# 5_-CONNECTORS.net
KiCad netlist of a schematic drawn in Altium Designer
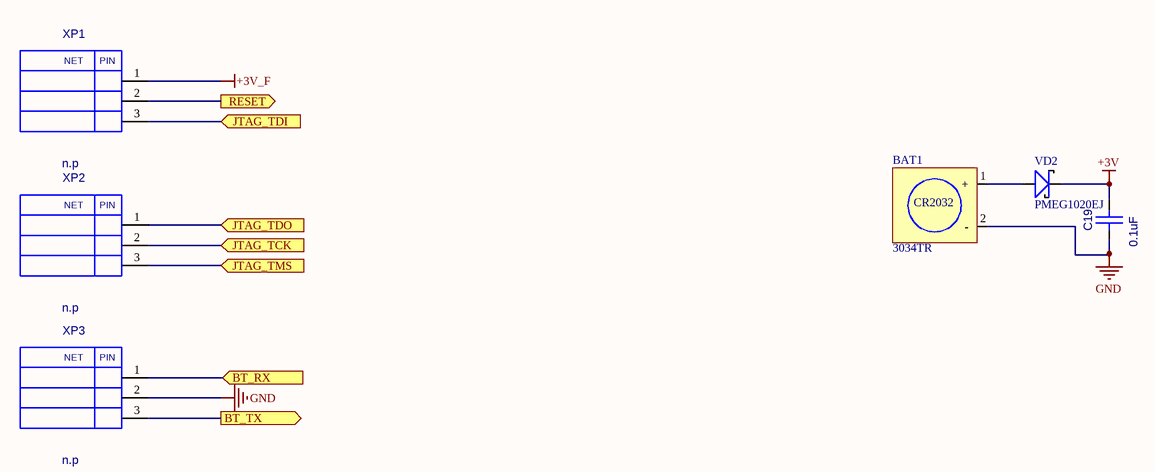
[diagram p0: [5]-CONNECTORS.SchDoc]

(export (version "E")
  (design (tool "Eeschema 10.0.6"))
  (components
    (comp (ref "BAT1")
      (value "3034TR")
      (footprint "3034-TR")
      (description "CR2032 holder smd")
      (libsource (lib "fizik_lib") (part "3034"))
    )
    (comp (ref "C19")
      (value "0.1uF")
      (footprint "CC0603")
      (description "CC0603")
      (libsource (lib "fizik_lib") (part "CC0603"))
    )
    (comp (ref "VD2")
      (value "PMEG1020EJ")
      (footprint "SOD323")
      (libsource (lib "fizik_lib") (part "PMEG2010"))
    )
    (comp (ref "XP1")
      (value "n.p")
      (footprint "PLS-03")
      (description "PLS03")
      (libsource (lib "fizik_lib") (part "PLS03"))
    )
    (comp (ref "XP2")
      (value "n.p")
      (footprint "PLS-03")
      (description "PLS03")
      (libsource (lib "fizik_lib") (part "PLS03"))
    )
    (comp (ref "XP3")
      (value "n.p")
      (footprint "PLS-03")
      (description "PLS03")
      (libsource (lib "fizik_lib") (part "PLS03"))
    )
  )
  (nets
    (net (code "1") (name "+3V") (class "Default")
      (node (ref "C19") (pin "2") (pinfunction "B_2") (pintype "passive"))
      (node (ref "VD2") (pin "2") (pinfunction "K_2") (pintype "passive"))
    )
    (net (code "2") (name "+3V_F") (class "Default")
      (node (ref "XP1") (pin "1") (pinfunction "1_1") (pintype "passive"))
    )
    (net (code "3") (name "/BT_RX") (class "Default")
      (node (ref "XP3") (pin "1") (pinfunction "1_1") (pintype "passive"))
    )
    (net (code "4") (name "/BT_TX") (class "Default")
      (node (ref "XP3") (pin "3") (pinfunction "3_3") (pintype "passive"))
    )
    (net (code "5") (name "/JTAG_TCK") (class "Default")
      (node (ref "XP2") (pin "2") (pinfunction "2_2") (pintype "passive"))
    )
    (net (code "6") (name "/JTAG_TDI") (class "Default")
      (node (ref "XP1") (pin "3") (pinfunction "3_3") (pintype "passive"))
    )
    (net (code "7") (name "/JTAG_TDO") (class "Default")
      (node (ref "XP2") (pin "1") (pinfunction "1_1") (pintype "passive"))
    )
    (net (code "8") (name "/JTAG_TMS") (class "Default")
      (node (ref "XP2") (pin "3") (pinfunction "3_3") (pintype "passive"))
    )
    (net (code "9") (name "/RESET") (class "Default")
      (node (ref "XP1") (pin "2") (pinfunction "2_2") (pintype "passive"))
    )
    (net (code "10") (name "GND") (class "Default")
      (node (ref "BAT1") (pin "2") (pinfunction "-_2") (pintype "passive"))
      (node (ref "C19") (pin "1") (pinfunction "A_1") (pintype "passive"))
      (node (ref "XP3") (pin "2") (pinfunction "2_2") (pintype "passive"))
    )
    (net (code "11") (name "Net-(BAT1-+)") (class "Default")
      (node (ref "BAT1") (pin "1") (pinfunction "+_1") (pintype "passive"))
      (node (ref "VD2") (pin "1") (pinfunction "A_1") (pintype "passive"))
    )
  )
)
